# ButtonBoard.net
KiCad netlist of a schematic drawn in EAGLE
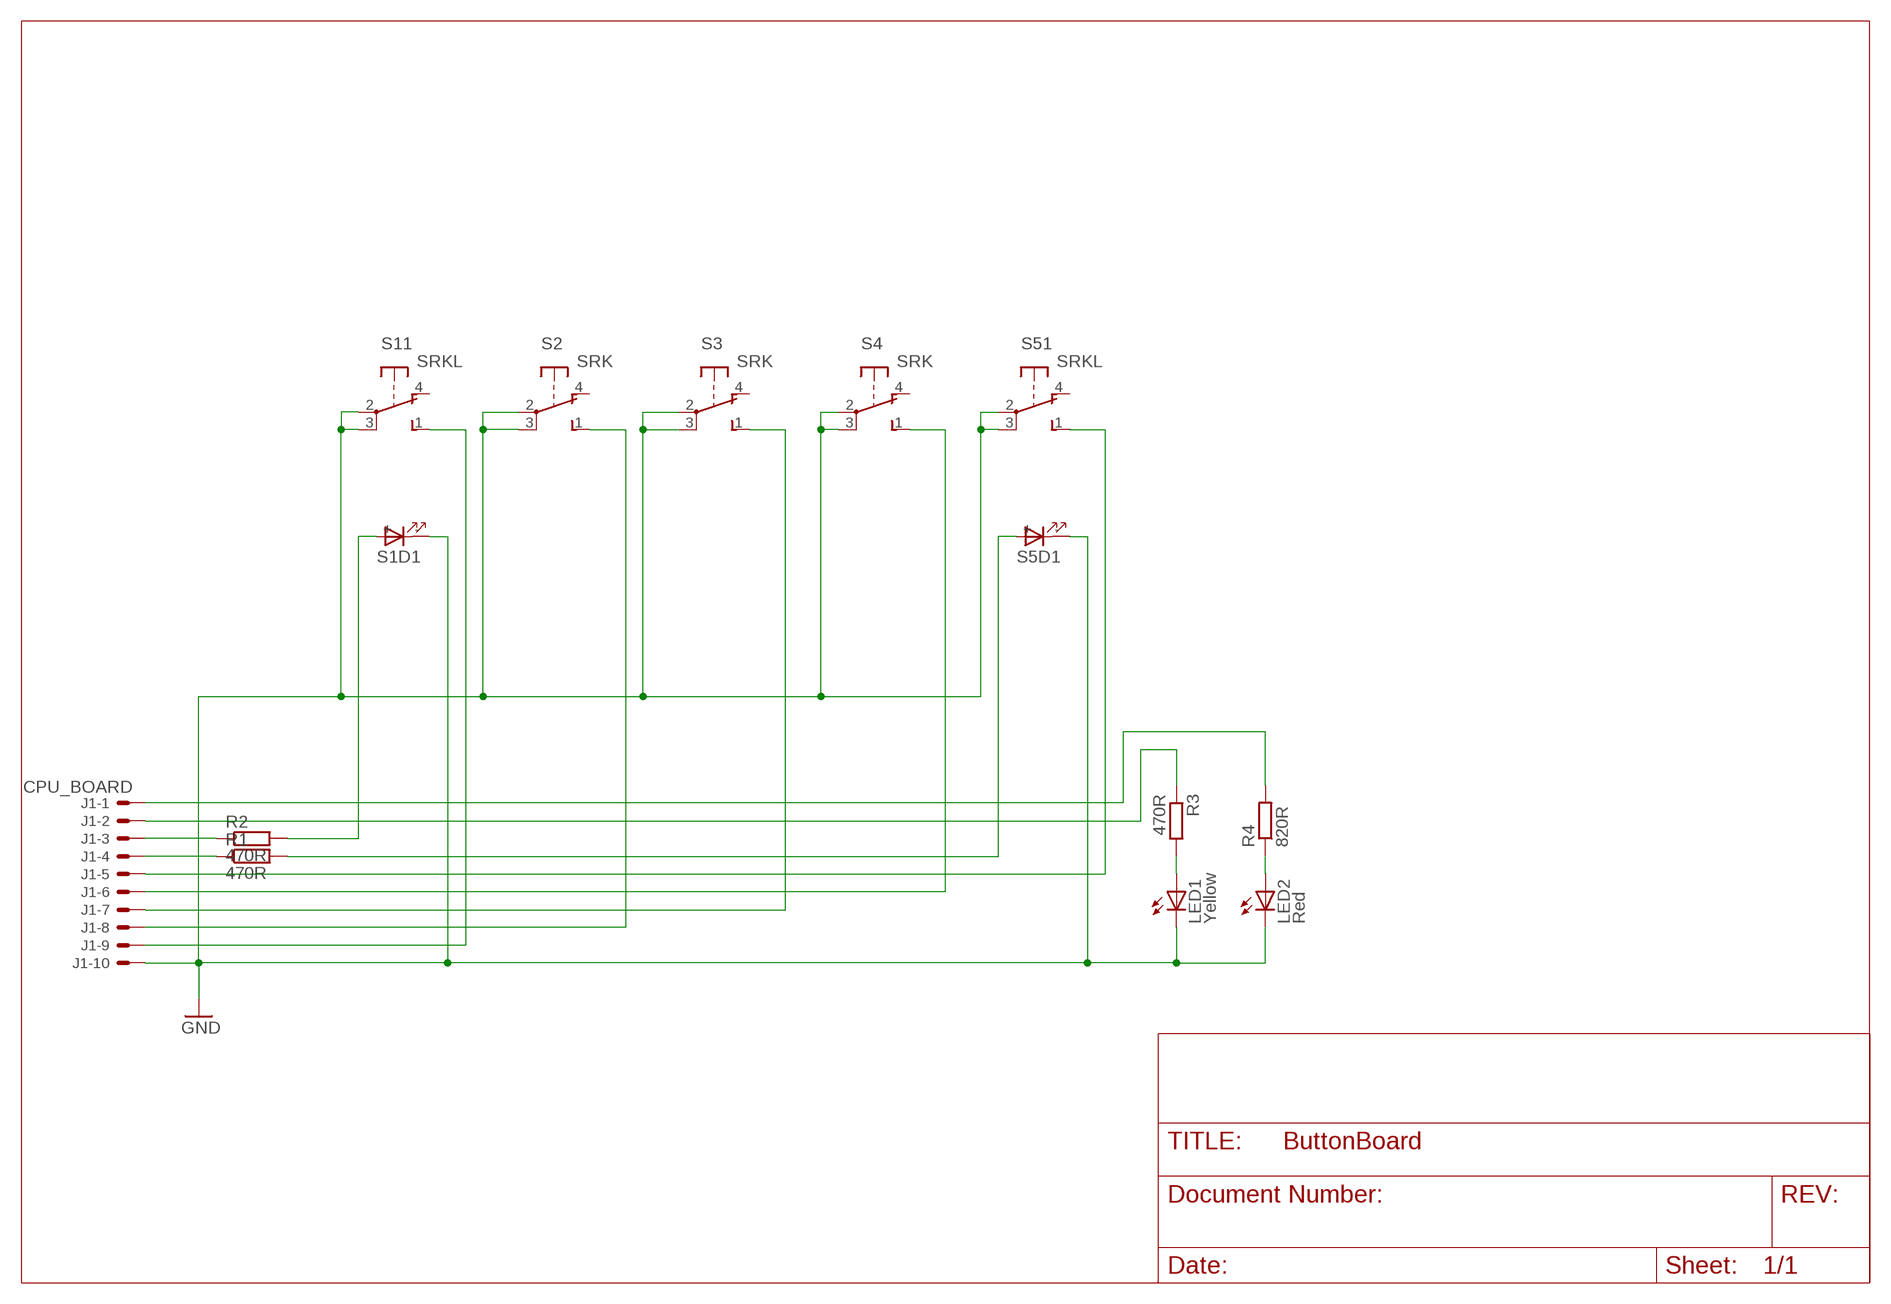
[diagram p0: schematic, sheet 1]

(export (version "E")
  (design (tool "Eeschema 10.0.6"))
  (components
    (comp (ref "J1")
      (value "CPU_BOARD")
      (footprint "eagle-import:7395-10")
      (libsource (lib "eagle-import") (part "22-?-1005-7108"))
    )
    (comp (ref "LED1")
      (value "Yellow")
      (footprint "eagle-import:LED3MM")
      (libsource (lib "eagle-import") (part "LED3MM"))
    )
    (comp (ref "LED2")
      (value "Red")
      (footprint "eagle-import:LED3MM")
      (libsource (lib "eagle-import") (part "LED3MM"))
    )
    (comp (ref "R1")
      (value "470R")
      (footprint "eagle-import:0207_10")
      (libsource (lib "eagle-import") (part "R-EU_0207/10"))
    )
    (comp (ref "R2")
      (value "470R")
      (footprint "eagle-import:0207_10")
      (libsource (lib "eagle-import") (part "R-EU_0207/10"))
    )
    (comp (ref "R3")
      (value "470R")
      (footprint "eagle-import:0207_10")
      (libsource (lib "eagle-import") (part "R-EU_0207/10"))
    )
    (comp (ref "R4")
      (value "820R")
      (footprint "eagle-import:0207_10")
      (libsource (lib "eagle-import") (part "R-EU_0207/10"))
    )
    (comp (ref "S1")
      (value "SRKL")
      (footprint "eagle-import:SRKL")
      (libsource (lib "eagle-import") (part "SRKL"))
    )
    (comp (ref "S2")
      (value "SRK")
      (footprint "eagle-import:SRK")
      (libsource (lib "eagle-import") (part "SRK"))
    )
    (comp (ref "S3")
      (value "SRK")
      (footprint "eagle-import:SRK")
      (libsource (lib "eagle-import") (part "SRK"))
    )
    (comp (ref "S4")
      (value "SRK")
      (footprint "eagle-import:SRK")
      (libsource (lib "eagle-import") (part "SRK"))
    )
    (comp (ref "S5")
      (value "SRKL")
      (footprint "eagle-import:SRKL")
      (libsource (lib "eagle-import") (part "SRKL"))
    )
  )
  (nets
    (net (code "1") (name "GND") (class "Default")
      (node (ref "J1") (pin "10") (pinfunction "S_10") (pintype "passive"))
      (node (ref "LED1") (pin "K") (pinfunction "C_K") (pintype "passive"))
      (node (ref "LED2") (pin "K") (pinfunction "C_K") (pintype "passive"))
      (node (ref "S1") (pin "-") (pinfunction "C_-") (pintype "passive"))
      (node (ref "S1") (pin "2") (pinfunction "P_2") (pintype "passive"))
      (node (ref "S1") (pin "3") (pinfunction "P_3") (pintype "passive"))
      (node (ref "S2") (pin "2") (pinfunction "P_2") (pintype "passive"))
      (node (ref "S2") (pin "3") (pinfunction "P_3") (pintype "passive"))
      (node (ref "S3") (pin "2") (pinfunction "P_2") (pintype "passive"))
      (node (ref "S3") (pin "3") (pinfunction "P_3") (pintype "passive"))
      (node (ref "S4") (pin "2") (pinfunction "P_2") (pintype "passive"))
      (node (ref "S4") (pin "3") (pinfunction "P_3") (pintype "passive"))
      (node (ref "S5") (pin "-") (pinfunction "C_-") (pintype "passive"))
      (node (ref "S5") (pin "2") (pinfunction "P_2") (pintype "passive"))
      (node (ref "S5") (pin "3") (pinfunction "P_3") (pintype "passive"))
    )
    (net (code "2") (name "Net-(J1A-S)") (class "Default")
      (node (ref "J1") (pin "1") (pinfunction "S_1") (pintype "passive"))
      (node (ref "R4") (pin "2") (pinfunction "2_2") (pintype "passive"))
    )
    (net (code "3") (name "Net-(J1C-S)") (class "Default")
      (node (ref "J1") (pin "2") (pinfunction "S_2") (pintype "passive"))
      (node (ref "R3") (pin "1") (pinfunction "1_1") (pintype "passive"))
    )
    (net (code "4") (name "Net-(J1D-S)") (class "Default")
      (node (ref "J1") (pin "3") (pinfunction "S_3") (pintype "passive"))
      (node (ref "R2") (pin "1") (pinfunction "1_1") (pintype "passive"))
    )
    (net (code "5") (name "Net-(J1E-S)") (class "Default")
      (node (ref "J1") (pin "4") (pinfunction "S_4") (pintype "passive"))
      (node (ref "R1") (pin "1") (pinfunction "1_1") (pintype "passive"))
    )
    (net (code "6") (name "Net-(J1F-S)") (class "Default")
      (node (ref "J1") (pin "5") (pinfunction "S_5") (pintype "passive"))
      (node (ref "S5") (pin "1") (pinfunction "S_1") (pintype "passive"))
    )
    (net (code "7") (name "Net-(J1G-S)") (class "Default")
      (node (ref "J1") (pin "6") (pinfunction "S_6") (pintype "passive"))
      (node (ref "S4") (pin "1") (pinfunction "S_1") (pintype "passive"))
    )
    (net (code "8") (name "Net-(J1H-S)") (class "Default")
      (node (ref "J1") (pin "7") (pinfunction "S_7") (pintype "passive"))
      (node (ref "S3") (pin "1") (pinfunction "S_1") (pintype "passive"))
    )
    (net (code "9") (name "Net-(J1I-S)") (class "Default")
      (node (ref "J1") (pin "8") (pinfunction "S_8") (pintype "passive"))
      (node (ref "S2") (pin "1") (pinfunction "S_1") (pintype "passive"))
    )
    (net (code "10") (name "Net-(J1J-S)") (class "Default")
      (node (ref "J1") (pin "9") (pinfunction "S_9") (pintype "passive"))
      (node (ref "S1") (pin "1") (pinfunction "S_1") (pintype "passive"))
    )
    (net (code "11") (name "Net-(LED1-PadA)") (class "Default")
      (node (ref "LED1") (pin "A") (pinfunction "A_A") (pintype "passive"))
      (node (ref "R3") (pin "2") (pinfunction "2_2") (pintype "passive"))
    )
    (net (code "12") (name "Net-(LED2-PadA)") (class "Default")
      (node (ref "LED2") (pin "A") (pinfunction "A_A") (pintype "passive"))
      (node (ref "R4") (pin "1") (pinfunction "1_1") (pintype "passive"))
    )
    (net (code "13") (name "Net-(S1B-A)") (class "Default")
      (node (ref "R2") (pin "2") (pinfunction "2_2") (pintype "passive"))
      (node (ref "S1") (pin "+") (pinfunction "A_+") (pintype "passive"))
    )
    (net (code "14") (name "Net-(S5B-A)") (class "Default")
      (node (ref "R1") (pin "2") (pinfunction "2_2") (pintype "passive"))
      (node (ref "S5") (pin "+") (pinfunction "A_+") (pintype "passive"))
    )
    (net (code "15") (name "unconnected-(S1A-O-Pad4)") (class "Default")
      (node (ref "S1") (pin "4") (pinfunction "O_4") (pintype "passive"))
    )
    (net (code "16") (name "unconnected-(S2-O-Pad4)") (class "Default")
      (node (ref "S2") (pin "4") (pinfunction "O_4") (pintype "passive"))
    )
    (net (code "17") (name "unconnected-(S3-O-Pad4)") (class "Default")
      (node (ref "S3") (pin "4") (pinfunction "O_4") (pintype "passive"))
    )
    (net (code "18") (name "unconnected-(S4-O-Pad4)") (class "Default")
      (node (ref "S4") (pin "4") (pinfunction "O_4") (pintype "passive"))
    )
    (net (code "19") (name "unconnected-(S5A-O-Pad4)") (class "Default")
      (node (ref "S5") (pin "4") (pinfunction "O_4") (pintype "passive"))
    )
  )
)
